# rfid_box.net
KiCad netlist of a schematic drawn in EAGLE
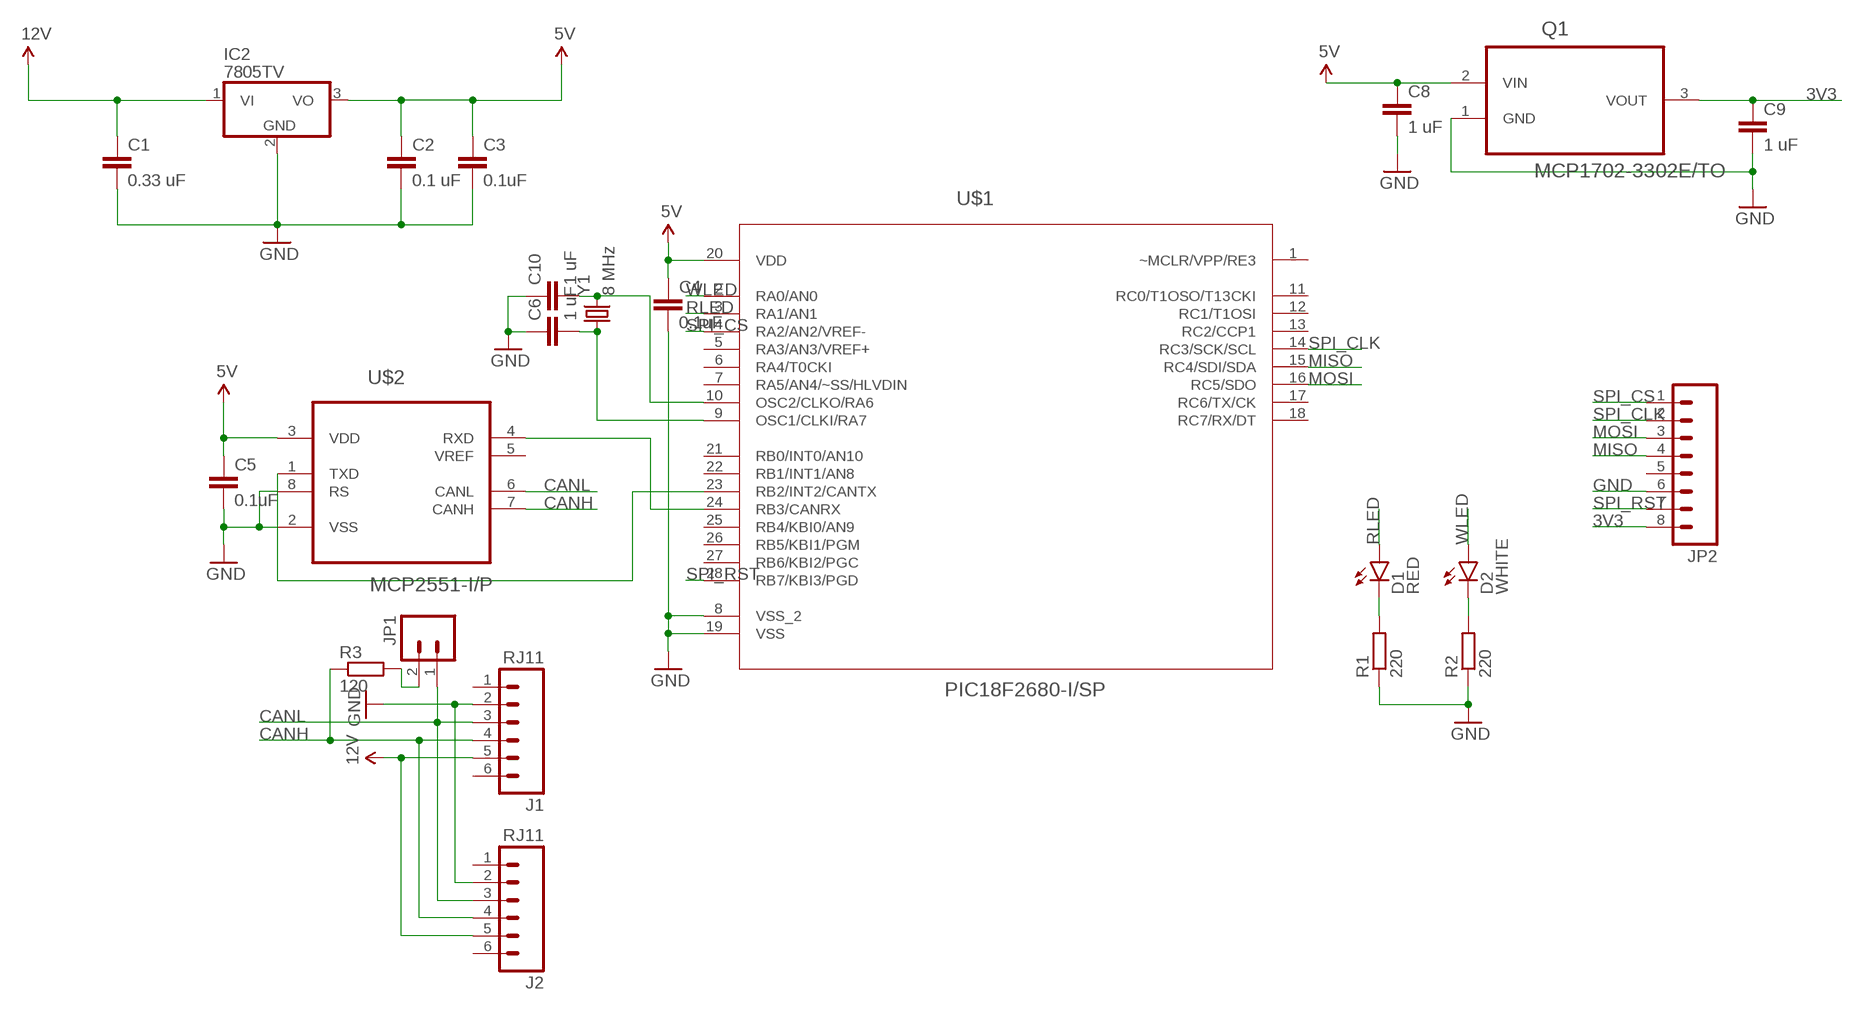
[diagram p0: schematic, sheet 1]

(export (version "E")
  (design (tool "Eeschema 10.0.6"))
  (components
    (comp (ref "C1")
      (value "0.33 uF")
      (footprint "eagle-import:C050-030X075")
      (libsource (lib "eagle-import") (part "C-EU050-030X075"))
    )
    (comp (ref "C2")
      (value "0.1 uF")
      (footprint "eagle-import:C050-030X075")
      (libsource (lib "eagle-import") (part "C-EU050-030X075"))
    )
    (comp (ref "C3")
      (value "0.1uF")
      (footprint "eagle-import:C050-030X075")
      (libsource (lib "eagle-import") (part "C-EU050-030X075"))
    )
    (comp (ref "C4")
      (value "0.1uF")
      (footprint "eagle-import:C050-030X075")
      (libsource (lib "eagle-import") (part "C-EU050-030X075"))
    )
    (comp (ref "C5")
      (value "0.1uF")
      (footprint "eagle-import:C050-030X075")
      (libsource (lib "eagle-import") (part "C-EU050-030X075"))
    )
    (comp (ref "C6")
      (value "1 uF")
      (footprint "eagle-import:C025-025X050")
      (libsource (lib "eagle-import") (part "C-EU025-025X050"))
    )
    (comp (ref "C8")
      (value "1 uF")
      (footprint "eagle-import:C050-030X075")
      (libsource (lib "eagle-import") (part "C-EU050-030X075"))
    )
    (comp (ref "C9")
      (value "1 uF")
      (footprint "eagle-import:C050-030X075")
      (libsource (lib "eagle-import") (part "C-EU050-030X075"))
    )
    (comp (ref "C10")
      (value "1 uF")
      (footprint "eagle-import:C025-025X050")
      (libsource (lib "eagle-import") (part "C-EU025-025X050"))
    )
    (comp (ref "D1")
      (value "RED")
      (footprint "eagle-import:LED5MM")
      (libsource (lib "eagle-import") (part "LED5MM"))
    )
    (comp (ref "D2")
      (value "WHITE")
      (footprint "eagle-import:LED5MM")
      (libsource (lib "eagle-import") (part "LED5MM"))
    )
    (comp (ref "IC2")
      (value "7805TV")
      (footprint "eagle-import:TO220V")
      (libsource (lib "eagle-import") (part "78TV05"))
    )
    (comp (ref "J1")
      (value "RJ11")
      (footprint "eagle-import:RJ11-6")
      (libsource (lib "eagle-import") (part "RJ11-6PTH"))
    )
    (comp (ref "J2")
      (value "RJ11")
      (footprint "eagle-import:RJ11-6")
      (libsource (lib "eagle-import") (part "RJ11-6PTH"))
    )
    (comp (ref "JP1")
      (value "M02PTH")
      (footprint "eagle-import:1X02")
      (libsource (lib "eagle-import") (part "M02PTH"))
    )
    (comp (ref "JP2")
      (value "M08")
      (footprint "eagle-import:1X08_ROUND")
      (libsource (lib "eagle-import") (part "M08"))
    )
    (comp (ref "Q1")
      (value "MCP1702-3302E/TO")
      (footprint "eagle-import:TO127P254X533-3")
      (libsource (lib "eagle-import") (part "MCP1702-3302E/TO"))
    )
    (comp (ref "R1")
      (value "220")
      (footprint "eagle-import:0207_10")
      (libsource (lib "eagle-import") (part "R-EU_0207/10"))
    )
    (comp (ref "R2")
      (value "220")
      (footprint "eagle-import:0207_10")
      (libsource (lib "eagle-import") (part "R-EU_0207/10"))
    )
    (comp (ref "R3")
      (value "120")
      (footprint "eagle-import:0207_10")
      (libsource (lib "eagle-import") (part "R-EU_0207/10"))
    )
    (comp (ref "U$1")
      (value "PIC18F2680-I/SP")
      (footprint "eagle-import:DIP254P762X508-28")
      (libsource (lib "eagle-import") (part "PIC18F2680-I/SP"))
    )
    (comp (ref "U$2")
      (value "MCP2551-I/P")
      (footprint "eagle-import:DIP254P762X432-8")
      (libsource (lib "eagle-import") (part "MCP2551-I/P"))
    )
    (comp (ref "Y1")
      (value "8 MHz")
      (footprint "eagle-import:HC49US")
      (libsource (lib "eagle-import") (part "CRYSTALHC49US"))
    )
  )
  (nets
    (net (code "1") (name "/3V3") (class "Default")
      (node (ref "C9") (pin "1") (pinfunction "1_1") (pintype "passive"))
      (node (ref "JP2") (pin "8") (pinfunction "8_8") (pintype "passive"))
      (node (ref "Q1") (pin "3") (pinfunction "VOUT_3") (pintype "output"))
    )
    (net (code "2") (name "/CANH") (class "Default")
      (node (ref "J1") (pin "4") (pinfunction "4_4") (pintype "passive"))
      (node (ref "J2") (pin "4") (pinfunction "4_4") (pintype "passive"))
      (node (ref "R3") (pin "1") (pinfunction "1_1") (pintype "passive"))
      (node (ref "U$2") (pin "7") (pinfunction "CANH_7") (pintype "bidirectional"))
    )
    (net (code "3") (name "/CANL") (class "Default")
      (node (ref "J1") (pin "3") (pinfunction "3_3") (pintype "passive"))
      (node (ref "J2") (pin "3") (pinfunction "3_3") (pintype "passive"))
      (node (ref "JP1") (pin "1") (pinfunction "1_1") (pintype "passive"))
      (node (ref "U$2") (pin "6") (pinfunction "CANL_6") (pintype "bidirectional"))
    )
    (net (code "4") (name "/MISO") (class "Default")
      (node (ref "JP2") (pin "4") (pinfunction "4_4") (pintype "passive"))
      (node (ref "U$1") (pin "15") (pinfunction "RC4/SDI/SDA_15") (pintype "bidirectional"))
    )
    (net (code "5") (name "/MOSI") (class "Default")
      (node (ref "JP2") (pin "3") (pinfunction "3_3") (pintype "passive"))
      (node (ref "U$1") (pin "16") (pinfunction "RC5/SDO_16") (pintype "bidirectional"))
    )
    (net (code "6") (name "/RLED") (class "Default")
      (node (ref "D1") (pin "A") (pinfunction "A_A") (pintype "passive"))
      (node (ref "U$1") (pin "3") (pinfunction "RA1/AN1_3") (pintype "bidirectional"))
    )
    (net (code "7") (name "/SPI_CLK") (class "Default")
      (node (ref "JP2") (pin "2") (pinfunction "2_2") (pintype "passive"))
      (node (ref "U$1") (pin "14") (pinfunction "RC3/SCK/SCL_14") (pintype "bidirectional"))
    )
    (net (code "8") (name "/SPI_CS") (class "Default")
      (node (ref "JP2") (pin "1") (pinfunction "1_1") (pintype "passive"))
      (node (ref "U$1") (pin "4") (pinfunction "RA2/AN2/VREF-_4") (pintype "bidirectional"))
    )
    (net (code "9") (name "/SPI_RST") (class "Default")
      (node (ref "JP2") (pin "7") (pinfunction "7_7") (pintype "passive"))
      (node (ref "U$1") (pin "28") (pinfunction "RB7/KBI3/PGD_28") (pintype "bidirectional"))
    )
    (net (code "10") (name "/WLED") (class "Default")
      (node (ref "D2") (pin "A") (pinfunction "A_A") (pintype "passive"))
      (node (ref "U$1") (pin "2") (pinfunction "RA0/AN0_2") (pintype "bidirectional"))
    )
    (net (code "11") (name "5V") (class "Default")
      (node (ref "C2") (pin "1") (pinfunction "1_1") (pintype "passive"))
      (node (ref "C3") (pin "1") (pinfunction "1_1") (pintype "passive"))
      (node (ref "C4") (pin "1") (pinfunction "1_1") (pintype "passive"))
      (node (ref "C5") (pin "1") (pinfunction "1_1") (pintype "passive"))
      (node (ref "C8") (pin "1") (pinfunction "1_1") (pintype "passive"))
      (node (ref "IC2") (pin "3") (pinfunction "VO_3") (pintype "passive"))
      (node (ref "Q1") (pin "2") (pinfunction "VIN_2") (pintype "input"))
      (node (ref "U$1") (pin "20") (pinfunction "VDD_20") (pintype "power_in"))
      (node (ref "U$2") (pin "3") (pinfunction "VDD_3") (pintype "power_in"))
    )
    (net (code "12") (name "12V") (class "Default")
      (node (ref "C1") (pin "1") (pinfunction "1_1") (pintype "passive"))
      (node (ref "IC2") (pin "1") (pinfunction "VI_1") (pintype "input"))
      (node (ref "J1") (pin "5") (pinfunction "5_5") (pintype "passive"))
      (node (ref "J2") (pin "5") (pinfunction "5_5") (pintype "passive"))
    )
    (net (code "13") (name "GND") (class "Default")
      (node (ref "C1") (pin "2") (pinfunction "2_2") (pintype "passive"))
      (node (ref "C10") (pin "1") (pinfunction "1_1") (pintype "passive"))
      (node (ref "C2") (pin "2") (pinfunction "2_2") (pintype "passive"))
      (node (ref "C3") (pin "2") (pinfunction "2_2") (pintype "passive"))
      (node (ref "C4") (pin "2") (pinfunction "2_2") (pintype "passive"))
      (node (ref "C5") (pin "2") (pinfunction "2_2") (pintype "passive"))
      (node (ref "C6") (pin "1") (pinfunction "1_1") (pintype "passive"))
      (node (ref "C8") (pin "2") (pinfunction "2_2") (pintype "passive"))
      (node (ref "C9") (pin "2") (pinfunction "2_2") (pintype "passive"))
      (node (ref "IC2") (pin "2") (pinfunction "GND_2") (pintype "passive"))
      (node (ref "J1") (pin "2") (pinfunction "2_2") (pintype "passive"))
      (node (ref "J2") (pin "2") (pinfunction "2_2") (pintype "passive"))
      (node (ref "JP2") (pin "6") (pinfunction "6_6") (pintype "passive"))
      (node (ref "Q1") (pin "1") (pinfunction "GND_1") (pintype "passive"))
      (node (ref "R1") (pin "1") (pinfunction "1_1") (pintype "passive"))
      (node (ref "R2") (pin "1") (pinfunction "1_1") (pintype "passive"))
      (node (ref "U$1") (pin "19") (pinfunction "VSS_19") (pintype "power_in"))
      (node (ref "U$1") (pin "8") (pinfunction "VSS_2_8") (pintype "power_in"))
      (node (ref "U$2") (pin "2") (pinfunction "VSS_2") (pintype "power_in"))
      (node (ref "U$2") (pin "8") (pinfunction "RS_8") (pintype "input"))
    )
    (net (code "14") (name "Net-(D1-C)") (class "Default")
      (node (ref "D1") (pin "K") (pinfunction "C_K") (pintype "passive"))
      (node (ref "R1") (pin "2") (pinfunction "2_2") (pintype "passive"))
    )
    (net (code "15") (name "Net-(D2-C)") (class "Default")
      (node (ref "D2") (pin "K") (pinfunction "C_K") (pintype "passive"))
      (node (ref "R2") (pin "2") (pinfunction "2_2") (pintype "passive"))
    )
    (net (code "16") (name "Net-(JP1-Pad2)") (class "Default")
      (node (ref "JP1") (pin "2") (pinfunction "2_2") (pintype "passive"))
      (node (ref "R3") (pin "2") (pinfunction "2_2") (pintype "passive"))
    )
    (net (code "17") (name "Net-(U$1-OSC1{slash}CLKI{slash}RA7)") (class "Default")
      (node (ref "C6") (pin "2") (pinfunction "2_2") (pintype "passive"))
      (node (ref "U$1") (pin "9") (pinfunction "OSC1/CLKI/RA7_9") (pintype "bidirectional"))
      (node (ref "Y1") (pin "1") (pinfunction "1_1") (pintype "passive"))
    )
    (net (code "18") (name "Net-(U$1-OSC2{slash}CLKO{slash}RA6)") (class "Default")
      (node (ref "C10") (pin "2") (pinfunction "2_2") (pintype "passive"))
      (node (ref "U$1") (pin "10") (pinfunction "OSC2/CLKO/RA6_10") (pintype "bidirectional"))
      (node (ref "Y1") (pin "2") (pinfunction "2_2") (pintype "passive"))
    )
    (net (code "19") (name "Net-(U$1-RB2{slash}INT2{slash}CANTX)") (class "Default")
      (node (ref "U$1") (pin "23") (pinfunction "RB2/INT2/CANTX_23") (pintype "bidirectional"))
      (node (ref "U$2") (pin "1") (pinfunction "TXD_1") (pintype "input"))
    )
    (net (code "20") (name "Net-(U$1-RB3{slash}CANRX)") (class "Default")
      (node (ref "U$1") (pin "24") (pinfunction "RB3/CANRX_24") (pintype "bidirectional"))
      (node (ref "U$2") (pin "4") (pinfunction "RXD_4") (pintype "output"))
    )
    (net (code "21") (name "unconnected-(J1-Pad1)") (class "Default")
      (node (ref "J1") (pin "1") (pinfunction "1_1") (pintype "passive"))
    )
    (net (code "22") (name "unconnected-(J1-Pad6)") (class "Default")
      (node (ref "J1") (pin "6") (pinfunction "6_6") (pintype "passive"))
    )
    (net (code "23") (name "unconnected-(J2-Pad1)") (class "Default")
      (node (ref "J2") (pin "1") (pinfunction "1_1") (pintype "passive"))
    )
    (net (code "24") (name "unconnected-(J2-Pad6)") (class "Default")
      (node (ref "J2") (pin "6") (pinfunction "6_6") (pintype "passive"))
    )
    (net (code "25") (name "unconnected-(JP2-Pad5)") (class "Default")
      (node (ref "JP2") (pin "5") (pinfunction "5_5") (pintype "passive"))
    )
    (net (code "26") (name "unconnected-(U$1-RA3{slash}AN3{slash}VREF+-Pad5)") (class "Default")
      (node (ref "U$1") (pin "5") (pinfunction "RA3/AN3/VREF+_5") (pintype "bidirectional"))
    )
    (net (code "27") (name "unconnected-(U$1-RA4{slash}T0CKI-Pad6)") (class "Default")
      (node (ref "U$1") (pin "6") (pinfunction "RA4/T0CKI_6") (pintype "bidirectional"))
    )
    (net (code "28") (name "unconnected-(U$1-RA5{slash}AN4{slash}~{SS{slash}HLVDIN}-Pad7)") (class "Default")
      (node (ref "U$1") (pin "7") (pinfunction "RA5/AN4/~{SS/HLVDIN}_7") (pintype "bidirectional"))
    )
    (net (code "29") (name "unconnected-(U$1-RB0{slash}INT0{slash}AN10-Pad21)") (class "Default")
      (node (ref "U$1") (pin "21") (pinfunction "RB0/INT0/AN10_21") (pintype "bidirectional"))
    )
    (net (code "30") (name "unconnected-(U$1-RB1{slash}INT1{slash}AN8-Pad22)") (class "Default")
      (node (ref "U$1") (pin "22") (pinfunction "RB1/INT1/AN8_22") (pintype "bidirectional"))
    )
    (net (code "31") (name "unconnected-(U$1-RB4{slash}KBI0{slash}AN9-Pad25)") (class "Default")
      (node (ref "U$1") (pin "25") (pinfunction "RB4/KBI0/AN9_25") (pintype "bidirectional"))
    )
    (net (code "32") (name "unconnected-(U$1-RB5{slash}KBI1{slash}PGM-Pad26)") (class "Default")
      (node (ref "U$1") (pin "26") (pinfunction "RB5/KBI1/PGM_26") (pintype "bidirectional"))
    )
    (net (code "33") (name "unconnected-(U$1-RB6{slash}KBI2{slash}PGC-Pad27)") (class "Default")
      (node (ref "U$1") (pin "27") (pinfunction "RB6/KBI2/PGC_27") (pintype "bidirectional"))
    )
    (net (code "34") (name "unconnected-(U$1-RC0{slash}T1OSO{slash}T13CKI-Pad11)") (class "Default")
      (node (ref "U$1") (pin "11") (pinfunction "RC0/T1OSO/T13CKI_11") (pintype "bidirectional"))
    )
    (net (code "35") (name "unconnected-(U$1-RC1{slash}T1OSI-Pad12)") (class "Default")
      (node (ref "U$1") (pin "12") (pinfunction "RC1/T1OSI_12") (pintype "bidirectional"))
    )
    (net (code "36") (name "unconnected-(U$1-RC2{slash}CCP1-Pad13)") (class "Default")
      (node (ref "U$1") (pin "13") (pinfunction "RC2/CCP1_13") (pintype "bidirectional"))
    )
    (net (code "37") (name "unconnected-(U$1-RC6{slash}TX{slash}CK-Pad17)") (class "Default")
      (node (ref "U$1") (pin "17") (pinfunction "RC6/TX/CK_17") (pintype "bidirectional"))
    )
    (net (code "38") (name "unconnected-(U$1-RC7{slash}RX{slash}DT-Pad18)") (class "Default")
      (node (ref "U$1") (pin "18") (pinfunction "RC7/RX/DT_18") (pintype "bidirectional"))
    )
    (net (code "39") (name "unconnected-(U$1-~{MCLR{slash}VPP{slash}RE3}-Pad1)") (class "Default")
      (node (ref "U$1") (pin "1") (pinfunction "~{MCLR/VPP/RE3}_1") (pintype "bidirectional"))
    )
    (net (code "40") (name "unconnected-(U$2-VREF-Pad5)") (class "Default")
      (node (ref "U$2") (pin "5") (pinfunction "VREF_5") (pintype "output"))
    )
  )
)
